# FET_Driver.net
KiCad netlist of a schematic drawn in Altium Designer
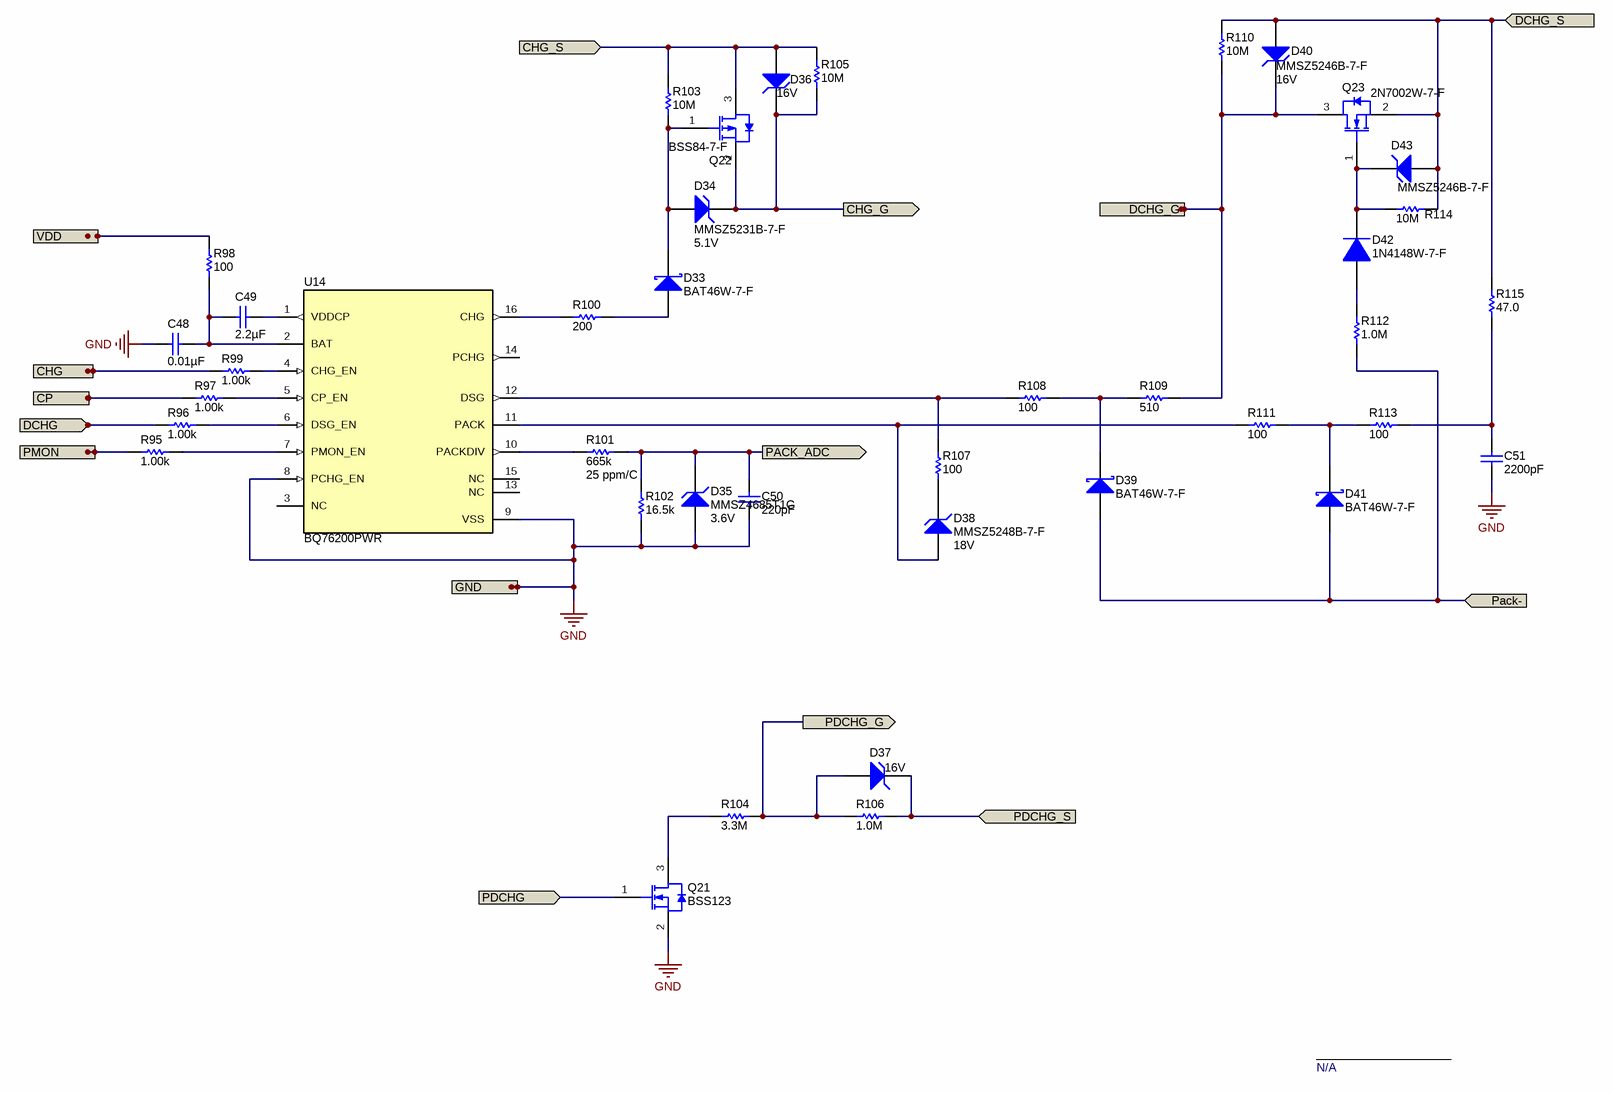
[diagram p0: FET Driver.SchDoc]

(export (version "E")
  (design (tool "Eeschema 10.0.6"))
  (components
    (comp (ref "C48")
      (value "GRM188R72A103KA01D")
      (footprint "0603")
      (description "CAP, CERM, 0.01 µF, 100 V,+/- 10%, X7R, 0603")
      (fields
        (field (name "VALUEDISPLAYED") "0.01µF")
        (field (name "MANUFACTURER") "MuRata")
        (field (name "PUBLISHER") "Texas Instruments")
      )
      (libsource (lib "Capacitor_Ceramic") (part "GRM188R72A103KA01D"))
    )
    (comp (ref "C49")
      (value "C2012X7R1V225K085AC")
      (footprint "0805_HV")
      (description "CAP, CERM, 2.2 µF, 35 V,+/- 10%, X7R, 0805")
      (fields
        (field (name "VALUEDISPLAYED") "2.2µF")
        (field (name "MANUFACTURER") "TDK")
        (field (name "PUBLISHER") "Texas Instruments")
      )
      (libsource (lib "Capacitor_Ceramic") (part "C2012X7R1V225K085AC"))
    )
    (comp (ref "C50")
      (value "GRM188R71H221KA01D")
      (footprint "0603")
      (description "CAP, CERM, 220 pF, 50 V,+/- 10%, X7R, 0603")
      (fields
        (field (name "VALUEDISPLAYED") "220pF")
        (field (name "MANUFACTURER") "MuRata")
        (field (name "PUBLISHER") "Texas Instruments")
      )
      (libsource (lib "Capacitor_Ceramic") (part "GRM188R71H221KA01D"))
    )
    (comp (ref "C51")
      (value "06031C222JAT2A")
      (footprint "0603")
      (description "CAP, CERM, 2200 pF, 100 V,+/- 5%, X7R, 0603")
      (fields
        (field (name "VALUEDISPLAYED") "2200pF")
        (field (name "MANUFACTURER") "AVX")
        (field (name "PUBLISHER") "Texas Instruments")
      )
      (libsource (lib "Capacitor_Ceramic") (part "06031C222JAT2A"))
    )
    (comp (ref "D33")
      (value "BAT46W-7-F")
      (footprint "SOD-123")
      (description "Diode, Schottky, 100 V, 0.15 A, SOD-123")
      (fields (field (name "MANUFACTURER") "Diodes Inc.") (field (name "PUBLISHER") "Texas Instruments"))
      (libsource (lib "Diode") (part "BAT46W-7-F"))
    )
    (comp (ref "D34")
      (value "MMSZ5231B-7-F")
      (footprint "SOD-123")
      (description "Diode, Zener, 5.1 V, 500 mW, SOD-123")
      (fields
        (field (name "ALTIUM_VALUE") "5.1V")
        (field (name "MANUFACTURER") "Diodes Inc.")
        (field (name "SYMBOLCREATOR") "a0412235")
        (field (name "PUBLISHER") "Texas Instruments")
      )
      (libsource (lib "ZenerDiodes") (part "MMSZ5231B-7-F"))
    )
    (comp (ref "D35")
      (value "MMSZ4685T1G")
      (footprint "SOD-123")
      (description "Diode, Zener, 3.6 V, 500 mW, SOD-123")
      (fields
        (field (name "ALTIUM_VALUE") "3.6V")
        (field (name "MANUFACTURER") "ON Semiconductor")
        (field (name "SYMBOLCREATOR") "a0412235")
        (field (name "PUBLISHER") "Texas Instruments")
      )
      (libsource (lib "ZenerDiodes") (part "MMSZ4685T1G"))
    )
    (comp (ref "D36")
      (value "16V")
      (footprint "SOD-123")
      (description "Diode, Zener, 16 V, 500 mW, SOD-123")
      (fields
        (field (name "PARTNUMBER") "MMSZ5246B-7-F")
        (field (name "MANUFACTURER") "Diodes Inc.")
        (field (name "SYMBOLCREATOR") "a0412235")
        (field (name "PUBLISHER") "Texas Instruments")
      )
      (libsource (lib "ZenerDiodes") (part "MMSZ5246B-7-F"))
    )
    (comp (ref "D37")
      (value "16V")
      (footprint "SOD-123")
      (description "Diode, Zener, 16 V, 500 mW, SOD-123")
      (fields
        (field (name "PARTNUMBER") "MMSZ5246B-7-F")
        (field (name "MANUFACTURER") "Diodes Inc.")
        (field (name "SYMBOLCREATOR") "a0412235")
        (field (name "PUBLISHER") "Texas Instruments")
      )
      (libsource (lib "ZenerDiodes") (part "MMSZ5246B-7-F"))
    )
    (comp (ref "D38")
      (value "MMSZ5248B-7-F")
      (footprint "SOD-123")
      (description "Diode, Zener, 18 V, 500 mW, SOD-123")
      (fields
        (field (name "ALTIUM_VALUE") "18V")
        (field (name "MANUFACTURER") "Diodes Inc.")
        (field (name "SYMBOLCREATOR") "a0412235")
        (field (name "PUBLISHER") "Texas Instruments")
      )
      (libsource (lib "ZenerDiodes") (part "MMSZ5248B-7-F"))
    )
    (comp (ref "D39")
      (value "BAT46W-7-F")
      (footprint "SOD-123")
      (description "Diode, Schottky, 100 V, 0.15 A, SOD-123")
      (fields (field (name "MANUFACTURER") "Diodes Inc.") (field (name "PUBLISHER") "Texas Instruments"))
      (libsource (lib "Diode") (part "BAT46W-7-F"))
    )
    (comp (ref "D40")
      (value "MMSZ5246B-7-F")
      (footprint "SOD-123")
      (description "Diode, Zener, 16 V, 500 mW, SOD-123")
      (fields
        (field (name "ALTIUM_VALUE") "16V")
        (field (name "MANUFACTURER") "Diodes Inc.")
        (field (name "SYMBOLCREATOR") "a0412235")
        (field (name "PUBLISHER") "Texas Instruments")
      )
      (libsource (lib "ZenerDiodes") (part "MMSZ5246B-7-F"))
    )
    (comp (ref "D41")
      (value "BAT46W-7-F")
      (footprint "SOD-123")
      (description "Diode, Schottky, 100 V, 0.15 A, SOD-123")
      (fields (field (name "MANUFACTURER") "Diodes Inc.") (field (name "PUBLISHER") "Texas Instruments"))
      (libsource (lib "Diode") (part "BAT46W-7-F"))
    )
    (comp (ref "D42")
      (value "1N4148W-7-F")
      (footprint "SOD-123")
      (description "Diode, Ultrafast, 100 V, 0.15 A, SOD-123")
      (fields (field (name "MANUFACTURER") "Diodes Inc.") (field (name "PUBLISHER") "Texas Instruments"))
      (libsource (lib "Diode") (part "1N4148W-7-F"))
    )
    (comp (ref "D43")
      (value "MMSZ5246B-7-F")
      (footprint "SOD-123")
      (description "Diode, Zener, 16 V, 500 mW, SOD-123")
      (fields
        (field (name "MANUFACTURER") "Diodes Inc.")
        (field (name "SYMBOLCREATOR") "a0412235")
        (field (name "PUBLISHER") "Texas Instruments")
      )
      (libsource (lib "ZenerDiodes") (part "MMSZ5246B-7-F"))
    )
    (comp (ref "Q21")
      (value "BSS123")
      (footprint "SOT-23")
      (description "MOSFET, N-CH, 100 V, 0.17 A, SOT-23")
      (fields
        (field (name "MANUFACTURER") "Fairchild Semiconductor")
        (field (name "PUBLISHER") "Texas Instruments")
      )
      (libsource (lib "FETs") (part "BSS123"))
    )
    (comp (ref "Q22")
      (value "BSS84-7-F")
      (footprint "SOT-23")
      (description "MOSFET, P-CH, -50 V, -0.13 A, SOT-23")
      (fields (field (name "MANUFACTURER") "Diodes Inc.") (field (name "PUBLISHER") "Texas Instruments"))
      (libsource (lib "FETs") (part "BSS84-7-F"))
    )
    (comp (ref "Q23")
      (value "2N7002W-7-F")
      (footprint "SOT-323")
      (description "MOSFET, N-CH, 60 V, 0.115 A, SOT-323")
      (fields (field (name "MANUFACTURER") "Diodes Inc.") (field (name "PUBLISHER") "Texas Instruments"))
      (libsource (lib "FETs") (part "2N7002W-7-F"))
    )
    (comp (ref "R95")
      (value "CRCW06031K00FKEA")
      (footprint "0603")
      (description "RES, 1.00 k, 1%, 0.1 W, 0603")
      (fields
        (field (name "VALUEDISPLAYED") "1.00k")
        (field (name "MANUFACTURER") "Vishay-Dale")
        (field (name "PUBLISHER") "Texas Instruments")
      )
      (libsource (lib "Resistor_0603") (part "CRCW06031K00FKEA"))
    )
    (comp (ref "R96")
      (value "CRCW06031K00FKEA")
      (footprint "0603")
      (description "RES, 1.00 k, 1%, 0.1 W, 0603")
      (fields
        (field (name "VALUEDISPLAYED") "1.00k")
        (field (name "MANUFACTURER") "Vishay-Dale")
        (field (name "PUBLISHER") "Texas Instruments")
      )
      (libsource (lib "Resistor_0603") (part "CRCW06031K00FKEA"))
    )
    (comp (ref "R97")
      (value "CRCW06031K00FKEA")
      (footprint "0603")
      (description "RES, 1.00 k, 1%, 0.1 W, 0603")
      (fields
        (field (name "VALUEDISPLAYED") "1.00k")
        (field (name "MANUFACTURER") "Vishay-Dale")
        (field (name "PUBLISHER") "Texas Instruments")
      )
      (libsource (lib "Resistor_0603") (part "CRCW06031K00FKEA"))
    )
    (comp (ref "R98")
      (value "CRCW0603100RFKEA")
      (footprint "0603")
      (description "RES, 100, 1%, 0.1 W, 0603")
      (fields
        (field (name "VALUEDISPLAYED") "100")
        (field (name "MANUFACTURER") "Vishay-Dale")
        (field (name "PUBLISHER") "Texas Instruments")
      )
      (libsource (lib "Resistor_0603") (part "CRCW0603100RFKEA"))
    )
    (comp (ref "R99")
      (value "CRCW06031K00FKEA")
      (footprint "0603")
      (description "RES, 1.00 k, 1%, 0.1 W, 0603")
      (fields
        (field (name "VALUEDISPLAYED") "1.00k")
        (field (name "MANUFACTURER") "Vishay-Dale")
        (field (name "PUBLISHER") "Texas Instruments")
      )
      (libsource (lib "Resistor_0603") (part "CRCW06031K00FKEA"))
    )
    (comp (ref "R100")
      (value "CRCW0603200RFKEA")
      (footprint "0603")
      (description "RES, 200, 1%, 0.1 W, 0603")
      (fields
        (field (name "VALUEDISPLAYED") "200")
        (field (name "MANUFACTURER") "Vishay-Dale")
        (field (name "PUBLISHER") "Texas Instruments")
      )
      (libsource (lib "Resistor_0603") (part "CRCW0603200RFKEA"))
    )
    (comp (ref "R101")
      (value "RT0603BRD07665KL")
      (footprint "0603")
      (description "RES, 665 k, 0.1%, 0.1 W, 0603")
      (fields
        (field (name "VALUEDISPLAYED") "665k")
        (field (name "MANUFACTURER") "Yageo America")
        (field (name "TEMPCO") "25 ppm/C")
        (field (name "PUBLISHER") "Texas Instruments")
      )
      (libsource (lib "Resistor_0603") (part "RT0603BRD07665KL"))
    )
    (comp (ref "R102")
      (value "RT0603BRD0716K5L")
      (footprint "0603")
      (description "RES, 16.5 k, 0.1%, 0.1 W, 0603")
      (fields
        (field (name "VALUEDISPLAYED") "16.5k")
        (field (name "MANUFACTURER") "Yageo America")
        (field (name "PUBLISHER") "Texas Instruments")
      )
      (libsource (lib "Resistor_0603") (part "RT0603BRD0716K5L"))
    )
    (comp (ref "R103")
      (value "CRCW060310M0JNEA")
      (footprint "0603")
      (description "RES, 10 M, 5%, 0.1 W, 0603")
      (fields
        (field (name "VALUEDISPLAYED") "10M")
        (field (name "MANUFACTURER") "Vishay-Dale")
        (field (name "PUBLISHER") "Texas Instruments")
      )
      (libsource (lib "Resistor_0603") (part "CRCW060310M0JNEA"))
    )
    (comp (ref "R104")
      (value "CRCW06033M30JNEA")
      (footprint "0603")
      (description "RES, 3.3 M, 5%, 0.1 W, 0603")
      (fields
        (field (name "VALUEDISPLAYED") "3.3M")
        (field (name "MANUFACTURER") "Vishay-Dale")
        (field (name "PUBLISHER") "Texas Instruments")
      )
      (libsource (lib "Resistor_0603") (part "CRCW06033M30JNEA"))
    )
    (comp (ref "R105")
      (value "CRCW060310M0JNEA")
      (footprint "0603")
      (description "RES, 10 M, 5%, 0.1 W, 0603")
      (fields
        (field (name "VALUEDISPLAYED") "10M")
        (field (name "MANUFACTURER") "Vishay-Dale")
        (field (name "PUBLISHER") "Texas Instruments")
      )
      (libsource (lib "Resistor_0603") (part "CRCW060310M0JNEA"))
    )
    (comp (ref "R106")
      (value "CRCW06031M00JNEA")
      (footprint "0603")
      (description "RES, 1.0 M, 5%, 0.1 W, 0603")
      (fields
        (field (name "VALUEDISPLAYED") "1.0M")
        (field (name "MANUFACTURER") "Vishay-Dale")
        (field (name "PUBLISHER") "Texas Instruments")
      )
      (libsource (lib "Resistor_0603") (part "CRCW06031M00JNEA"))
    )
    (comp (ref "R107")
      (value "CRCW0603100RFKEA")
      (footprint "0603")
      (description "RES, 100, 1%, 0.1 W, 0603")
      (fields
        (field (name "VALUEDISPLAYED") "100")
        (field (name "MANUFACTURER") "Vishay-Dale")
        (field (name "PUBLISHER") "Texas Instruments")
      )
      (libsource (lib "Resistor_0603") (part "CRCW0603100RFKEA"))
    )
    (comp (ref "R108")
      (value "CRCW0603100RFKEA")
      (footprint "0603S")
      (description "RES, 100, 1%, 0.1 W, 0603")
      (fields
        (field (name "VALUEDISPLAYED") "100")
        (field (name "MANUFACTURER") "Vishay-Dale")
        (field (name "PUBLISHER") "Texas Instruments")
      )
      (libsource (lib "Resistor_0603") (part "CRCW0603100RFKEA"))
    )
    (comp (ref "R109")
      (value "CRCW0603510RJNEA")
      (footprint "0603")
      (description "RES, 510, 5%, 0.1 W, 0603")
      (fields
        (field (name "VALUEDISPLAYED") "510")
        (field (name "MANUFACTURER") "Vishay-Dale")
        (field (name "PUBLISHER") "Texas Instruments")
      )
      (libsource (lib "Resistor_0603") (part "CRCW0603510RJNEA"))
    )
    (comp (ref "R110")
      (value "CRCW060310M0JNEA")
      (footprint "0603")
      (description "RES, 10 M, 5%, 0.1 W, 0603")
      (fields
        (field (name "VALUEDISPLAYED") "10M")
        (field (name "MANUFACTURER") "Vishay-Dale")
        (field (name "PUBLISHER") "Texas Instruments")
      )
      (libsource (lib "Resistor_0603") (part "CRCW060310M0JNEA"))
    )
    (comp (ref "R111")
      (value "CRCW0603100RFKEA")
      (footprint "0603")
      (description "RES, 100, 1%, 0.1 W, 0603")
      (fields
        (field (name "VALUEDISPLAYED") "100")
        (field (name "MANUFACTURER") "Vishay-Dale")
        (field (name "PUBLISHER") "Texas Instruments")
      )
      (libsource (lib "Resistor_0603") (part "CRCW0603100RFKEA"))
    )
    (comp (ref "R112")
      (value "CRCW06031M00JNEA")
      (footprint "0603")
      (description "RES, 1.0 M, 5%, 0.1 W, 0603")
      (fields
        (field (name "VALUEDISPLAYED") "1.0M")
        (field (name "MANUFACTURER") "Vishay-Dale")
        (field (name "PUBLISHER") "Texas Instruments")
      )
      (libsource (lib "Resistor_0603") (part "CRCW06031M00JNEA"))
    )
    (comp (ref "R113")
      (value "CRCW0603100RFKEA")
      (footprint "0603")
      (description "RES, 100, 1%, 0.1 W, 0603")
      (fields
        (field (name "VALUEDISPLAYED") "100")
        (field (name "MANUFACTURER") "Vishay-Dale")
        (field (name "PUBLISHER") "Texas Instruments")
      )
      (libsource (lib "Resistor_0603") (part "CRCW0603100RFKEA"))
    )
    (comp (ref "R114")
      (value "CRCW060310M0JNEA")
      (footprint "0603")
      (description "RES, 10 M, 5%, 0.1 W, 0603")
      (fields
        (field (name "VALUEDISPLAYED") "10M")
        (field (name "MANUFACTURER") "Vishay-Dale")
        (field (name "PUBLISHER") "Texas Instruments")
      )
      (libsource (lib "Resistor_0603") (part "CRCW060310M0JNEA"))
    )
    (comp (ref "R115")
      (value "RC0603FR-0747RL")
      (footprint "0603")
      (description "RES, 47.0, 1%, 0.1 W, 0603")
      (fields
        (field (name "VALUEDISPLAYED") "47.0")
        (field (name "MANUFACTURER") "Yageo America")
        (field (name "PUBLISHER") "Texas Instruments")
      )
      (libsource (lib "Resistor_0603") (part "RC0603FR-0747RL"))
    )
    (comp (ref "U14")
      (value "BQ76200PWR")
      (footprint "PW0016A_L")
      (description "High-Side N-Channel FET Driver, PW0016A (TSSOP-16)")
      (fields
        (field (name "PARTNUMBER") "BQ76200PWR")
        (field (name "MANUFACTURER") "Texas Instruments")
        (field (name "ALTERNATE PARTNUMBER") "BQ76200PW")
        (field (name "PUBLISHER") "Texas Instruments")
      )
      (libsource (lib "Altium Vault - TI") (part "BQ76200"))
    )
  )
  (nets
    (net (code "1") (name "/CHG") (class "Default")
      (node (ref "R99") (pin "1") (pinfunction "1_1") (pintype "passive"))
    )
    (net (code "2") (name "/CHG_G") (class "Default")
      (node (ref "D34") (pin "1") (pinfunction "K_1") (pintype "passive"))
      (node (ref "D36") (pin "1") (pinfunction "K_1") (pintype "passive"))
      (node (ref "Q22") (pin "2") (pinfunction "S_2") (pintype "passive"))
      (node (ref "R105") (pin "1") (pinfunction "1_1") (pintype "passive"))
    )
    (net (code "3") (name "/CHG_S") (class "Default")
      (node (ref "D36") (pin "2") (pinfunction "A_2") (pintype "passive"))
      (node (ref "Q22") (pin "3") (pinfunction "D_3") (pintype "passive"))
      (node (ref "R103") (pin "2") (pinfunction "2_2") (pintype "passive"))
      (node (ref "R105") (pin "2") (pinfunction "2_2") (pintype "passive"))
    )
    (net (code "4") (name "/CP") (class "Default")
      (node (ref "R97") (pin "1") (pinfunction "1_1") (pintype "passive"))
    )
    (net (code "5") (name "/DCHG") (class "Default")
      (node (ref "R96") (pin "1") (pinfunction "1_1") (pintype "passive"))
    )
    (net (code "6") (name "/DCHG_G") (class "Default")
      (node (ref "D40") (pin "1") (pinfunction "K_1") (pintype "passive"))
      (node (ref "Q23") (pin "3") (pinfunction "D_3") (pintype "passive"))
      (node (ref "R109") (pin "2") (pinfunction "2_2") (pintype "passive"))
      (node (ref "R110") (pin "1") (pinfunction "1_1") (pintype "passive"))
    )
    (net (code "7") (name "/DCHG_S") (class "Default")
      (node (ref "D40") (pin "2") (pinfunction "A_2") (pintype "passive"))
      (node (ref "D43") (pin "2") (pinfunction "A_2") (pintype "passive"))
      (node (ref "Q23") (pin "2") (pinfunction "S_2") (pintype "passive"))
      (node (ref "R110") (pin "2") (pinfunction "2_2") (pintype "passive"))
      (node (ref "R114") (pin "1") (pinfunction "1_1") (pintype "passive"))
      (node (ref "R115") (pin "2") (pinfunction "2_2") (pintype "passive"))
    )
    (net (code "8") (name "/PACK_ADC") (class "Default")
      (node (ref "C50") (pin "1") (pinfunction "1_1") (pintype "passive"))
      (node (ref "D35") (pin "1") (pinfunction "K_1") (pintype "passive"))
      (node (ref "R101") (pin "2") (pinfunction "2_2") (pintype "passive"))
      (node (ref "R102") (pin "2") (pinfunction "2_2") (pintype "passive"))
    )
    (net (code "9") (name "/PDCHG") (class "Default")
      (node (ref "Q21") (pin "1") (pinfunction "G_1") (pintype "passive"))
    )
    (net (code "10") (name "/PDCHG_G") (class "Default")
      (node (ref "D37") (pin "2") (pinfunction "A_2") (pintype "passive"))
      (node (ref "R104") (pin "2") (pinfunction "2_2") (pintype "passive"))
      (node (ref "R106") (pin "1") (pinfunction "1_1") (pintype "passive"))
    )
    (net (code "11") (name "/PDCHG_S") (class "Default")
      (node (ref "D37") (pin "1") (pinfunction "K_1") (pintype "passive"))
      (node (ref "R106") (pin "2") (pinfunction "2_2") (pintype "passive"))
    )
    (net (code "12") (name "/PMON") (class "Default")
      (node (ref "R95") (pin "1") (pinfunction "1_1") (pintype "passive"))
    )
    (net (code "13") (name "/Pack-") (class "Default")
      (node (ref "D39") (pin "2") (pinfunction "A_2") (pintype "passive"))
      (node (ref "D41") (pin "2") (pinfunction "A_2") (pintype "passive"))
      (node (ref "R112") (pin "1") (pinfunction "1_1") (pintype "passive"))
    )
    (net (code "14") (name "/VDD") (class "Default")
      (node (ref "R98") (pin "2") (pinfunction "2_2") (pintype "passive"))
    )
    (net (code "15") (name "GND") (class "Default")
      (node (ref "C48") (pin "2") (pinfunction "2_2") (pintype "passive"))
      (node (ref "C50") (pin "2") (pinfunction "2_2") (pintype "passive"))
      (node (ref "C51") (pin "2") (pinfunction "2_2") (pintype "passive"))
      (node (ref "D35") (pin "2") (pinfunction "A_2") (pintype "passive"))
      (node (ref "Q21") (pin "2") (pinfunction "S_2") (pintype "passive"))
      (node (ref "R102") (pin "1") (pinfunction "1_1") (pintype "passive"))
      (node (ref "U14") (pin "8") (pinfunction "PCHG_EN_8") (pintype "input"))
      (node (ref "U14") (pin "9") (pinfunction "VSS_9") (pintype "power_in"))
    )
    (net (code "16") (name "Net-(C51-Pad1)") (class "Default")
      (node (ref "C51") (pin "1") (pinfunction "1_1") (pintype "passive"))
      (node (ref "R113") (pin "2") (pinfunction "2_2") (pintype "passive"))
      (node (ref "R115") (pin "1") (pinfunction "1_1") (pintype "passive"))
    )
    (net (code "17") (name "Net-(D33-A)") (class "Default")
      (node (ref "D33") (pin "2") (pinfunction "A_2") (pintype "passive"))
      (node (ref "R100") (pin "2") (pinfunction "2_2") (pintype "passive"))
    )
    (net (code "18") (name "Net-(D33-K)") (class "Default")
      (node (ref "D33") (pin "1") (pinfunction "K_1") (pintype "passive"))
      (node (ref "D34") (pin "2") (pinfunction "A_2") (pintype "passive"))
      (node (ref "Q22") (pin "1") (pinfunction "G_1") (pintype "passive"))
      (node (ref "R103") (pin "1") (pinfunction "1_1") (pintype "passive"))
    )
    (net (code "19") (name "Net-(D38-A)") (class "Default")
      (node (ref "D38") (pin "2") (pinfunction "A_2") (pintype "passive"))
      (node (ref "R111") (pin "1") (pinfunction "1_1") (pintype "passive"))
      (node (ref "U14") (pin "11") (pinfunction "PACK_11") (pintype "power_in"))
    )
    (net (code "20") (name "Net-(D38-K)") (class "Default")
      (node (ref "D38") (pin "1") (pinfunction "K_1") (pintype "passive"))
      (node (ref "R107") (pin "1") (pinfunction "1_1") (pintype "passive"))
    )
    (net (code "21") (name "Net-(D39-K)") (class "Default")
      (node (ref "D39") (pin "1") (pinfunction "K_1") (pintype "passive"))
      (node (ref "R108") (pin "2") (pinfunction "2_2") (pintype "passive"))
      (node (ref "R109") (pin "1") (pinfunction "1_1") (pintype "passive"))
    )
    (net (code "22") (name "Net-(D41-K)") (class "Default")
      (node (ref "D41") (pin "1") (pinfunction "K_1") (pintype "passive"))
      (node (ref "R111") (pin "2") (pinfunction "2_2") (pintype "passive"))
      (node (ref "R113") (pin "1") (pinfunction "1_1") (pintype "passive"))
    )
    (net (code "23") (name "Net-(D42-A)") (class "Default")
      (node (ref "D42") (pin "2") (pinfunction "A_2") (pintype "passive"))
      (node (ref "R112") (pin "2") (pinfunction "2_2") (pintype "passive"))
    )
    (net (code "24") (name "Net-(D42-K)") (class "Default")
      (node (ref "D42") (pin "1") (pinfunction "K_1") (pintype "passive"))
      (node (ref "D43") (pin "1") (pinfunction "K_1") (pintype "passive"))
      (node (ref "Q23") (pin "1") (pinfunction "G_1") (pintype "passive"))
      (node (ref "R114") (pin "2") (pinfunction "2_2") (pintype "passive"))
    )
    (net (code "25") (name "Net-(Q21-D)") (class "Default")
      (node (ref "Q21") (pin "3") (pinfunction "D_3") (pintype "passive"))
      (node (ref "R104") (pin "1") (pinfunction "1_1") (pintype "passive"))
    )
    (net (code "26") (name "Net-(U14-BAT)") (class "Default")
      (node (ref "C48") (pin "1") (pinfunction "1_1") (pintype "passive"))
      (node (ref "C49") (pin "2") (pinfunction "2_2") (pintype "passive"))
      (node (ref "R98") (pin "1") (pinfunction "1_1") (pintype "passive"))
      (node (ref "U14") (pin "2") (pinfunction "BAT_2") (pintype "power_in"))
    )
    (net (code "27") (name "Net-(U14-CHG)") (class "Default")
      (node (ref "R100") (pin "1") (pinfunction "1_1") (pintype "passive"))
      (node (ref "U14") (pin "16") (pinfunction "CHG_16") (pintype "output"))
    )
    (net (code "28") (name "Net-(U14-CHG_EN)") (class "Default")
      (node (ref "R99") (pin "2") (pinfunction "2_2") (pintype "passive"))
      (node (ref "U14") (pin "4") (pinfunction "CHG_EN_4") (pintype "input"))
    )
    (net (code "29") (name "Net-(U14-CP_EN)") (class "Default")
      (node (ref "R97") (pin "2") (pinfunction "2_2") (pintype "passive"))
      (node (ref "U14") (pin "5") (pinfunction "CP_EN_5") (pintype "input"))
    )
    (net (code "30") (name "Net-(U14-DSG)") (class "Default")
      (node (ref "R107") (pin "2") (pinfunction "2_2") (pintype "passive"))
      (node (ref "R108") (pin "1") (pinfunction "1_1") (pintype "passive"))
      (node (ref "U14") (pin "12") (pinfunction "DSG_12") (pintype "output"))
    )
    (net (code "31") (name "Net-(U14-DSG_EN)") (class "Default")
      (node (ref "R96") (pin "2") (pinfunction "2_2") (pintype "passive"))
      (node (ref "U14") (pin "6") (pinfunction "DSG_EN_6") (pintype "input"))
    )
    (net (code "32") (name "Net-(U14-PACKDIV)") (class "Default")
      (node (ref "R101") (pin "1") (pinfunction "1_1") (pintype "passive"))
      (node (ref "U14") (pin "10") (pinfunction "PACKDIV_10") (pintype "output"))
    )
    (net (code "33") (name "Net-(U14-PMON_EN)") (class "Default")
      (node (ref "R95") (pin "2") (pinfunction "2_2") (pintype "passive"))
      (node (ref "U14") (pin "7") (pinfunction "PMON_EN_7") (pintype "input"))
    )
    (net (code "34") (name "Net-(U14-VDDCP)") (class "Default")
      (node (ref "C49") (pin "1") (pinfunction "1_1") (pintype "passive"))
      (node (ref "U14") (pin "1") (pinfunction "VDDCP_1") (pintype "output"))
    )
    (net (code "35") (name "unconnected-(U14-NC-Pad3)") (class "Default")
      (node (ref "U14") (pin "3") (pinfunction "NC_3") (pintype "passive"))
    )
    (net (code "36") (name "unconnected-(U14-NC-Pad13)") (class "Default")
      (node (ref "U14") (pin "13") (pinfunction "NC_13") (pintype "passive"))
    )
    (net (code "37") (name "unconnected-(U14-NC-Pad15)") (class "Default")
      (node (ref "U14") (pin "15") (pinfunction "NC_15") (pintype "passive"))
    )
    (net (code "38") (name "unconnected-(U14-PCHG-Pad14)") (class "Default")
      (node (ref "U14") (pin "14") (pinfunction "PCHG_14") (pintype "output"))
    )
  )
)
